# WL_CON.net
KiCad netlist of a schematic drawn in Altium Designer
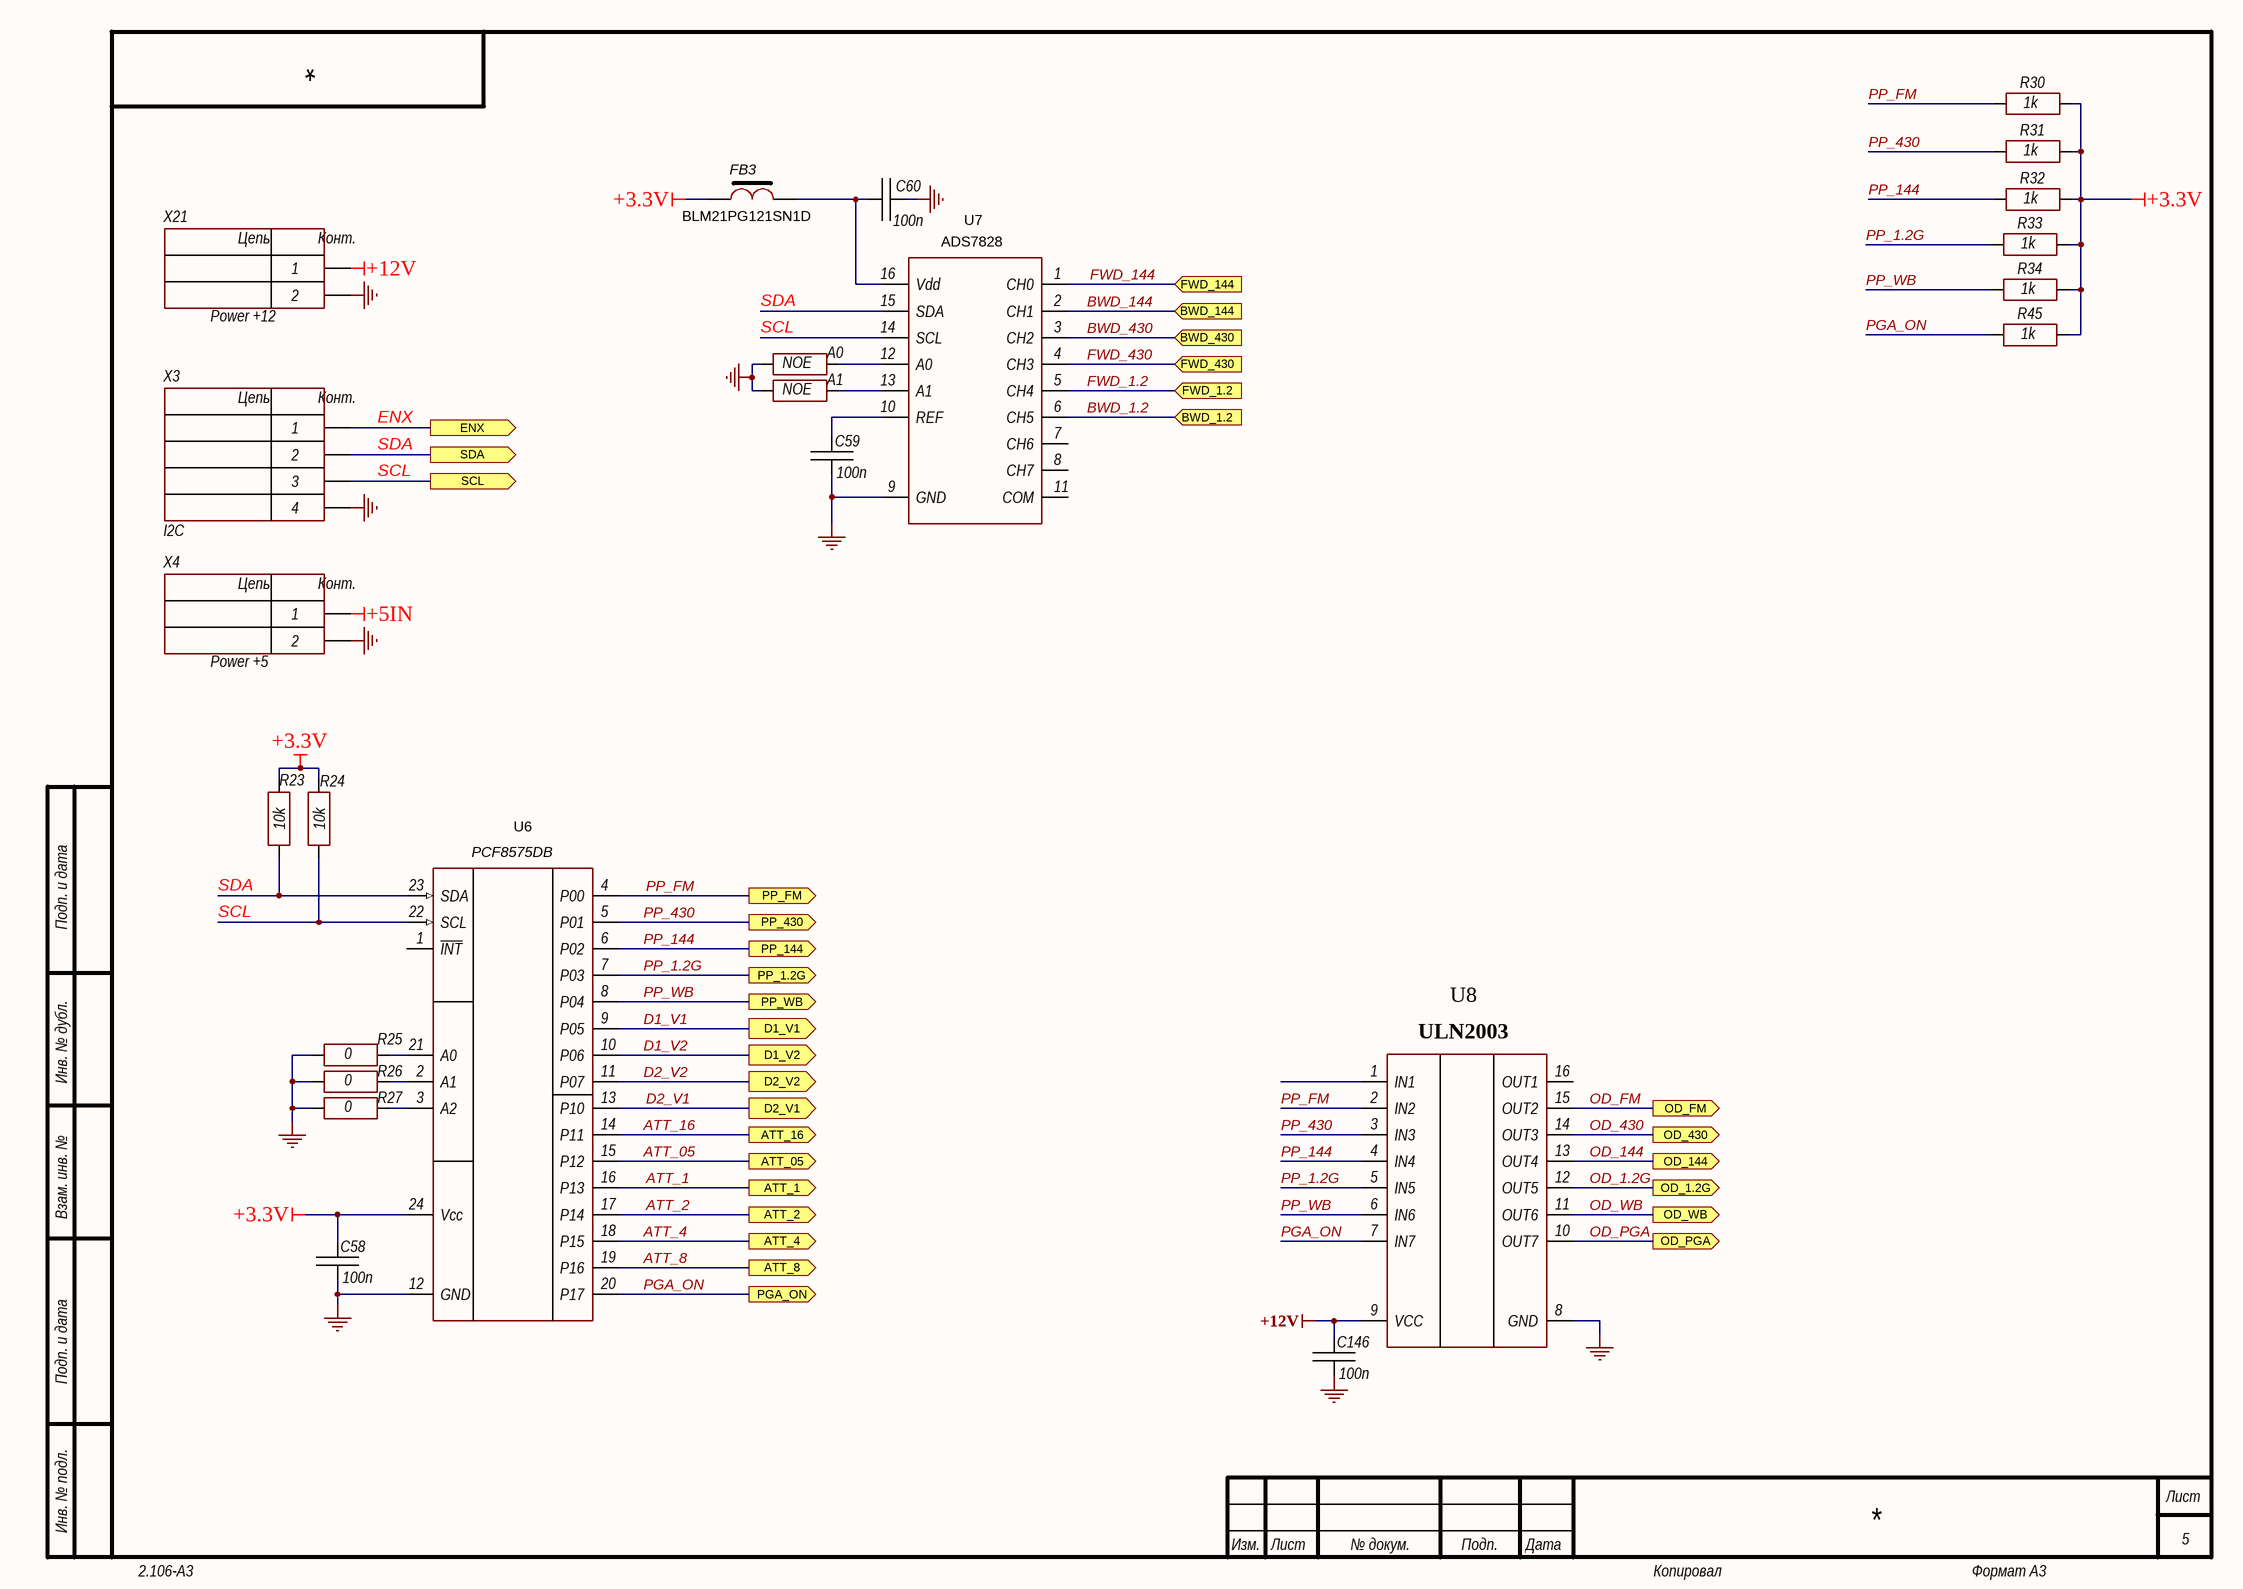
[diagram p0: WL_CON.SchDoc]

(export (version "E")
  (design (tool "Eeschema 10.0.6"))
  (components
    (comp (ref "A0")
      (value "NOE")
      (footprint "standard:CH0805R")
      (libsource (lib "Discrete") (part "Resistor"))
    )
    (comp (ref "A1")
      (value "NOE")
      (footprint "standard:CH0805R")
      (libsource (lib "Discrete") (part "Resistor"))
    )
    (comp (ref "C58")
      (value "100n")
      (footprint "standard:CH0805C")
      (libsource (lib "Discrete") (part "Capacitor"))
    )
    (comp (ref "C59")
      (value "100n")
      (footprint "standard:CH0805C")
      (libsource (lib "Discrete") (part "Capacitor"))
    )
    (comp (ref "C60")
      (value "100n")
      (footprint "standard:CH0805C")
      (libsource (lib "Discrete") (part "Capacitor"))
    )
    (comp (ref "C146")
      (value "100n")
      (footprint "standard:CH0805C")
      (libsource (lib "") (part "Capacitor_1"))
    )
    (comp (ref "FB3")
      (value "BLM21PG121SN1D")
      (footprint "CH0805L")
      (libsource (lib "Discrete") (part "FB-1"))
    )
    (comp (ref "R23") (value "10k") (footprint "standard:CH0805R") (libsource (lib "") (part "Resistor_1")))
    (comp (ref "R24") (value "10k") (footprint "standard:CH0805R") (libsource (lib "") (part "Resistor_1")))
    (comp (ref "R25")
      (value "0")
      (footprint "standard:CH0805R")
      (libsource (lib "Discrete") (part "Resistor"))
    )
    (comp (ref "R26")
      (value "0")
      (footprint "standard:CH0805R")
      (libsource (lib "Discrete") (part "Resistor"))
    )
    (comp (ref "R27")
      (value "0")
      (footprint "standard:CH0805R")
      (libsource (lib "Discrete") (part "Resistor"))
    )
    (comp (ref "R30")
      (value "1k")
      (footprint "standard:CH0603R")
      (libsource (lib "Discrete") (part "Resistor"))
    )
    (comp (ref "R31")
      (value "1k")
      (footprint "standard:CH0603R")
      (libsource (lib "Discrete") (part "Resistor"))
    )
    (comp (ref "R32")
      (value "1k")
      (footprint "standard:CH0603R")
      (libsource (lib "Discrete") (part "Resistor"))
    )
    (comp (ref "R33") (value "1k") (footprint "standard:CH0603R") (libsource (lib "") (part "Resistor_2")))
    (comp (ref "R34")
      (value "1k")
      (footprint "standard:CH0603R")
      (libsource (lib "Discrete") (part "Resistor"))
    )
    (comp (ref "R45")
      (value "1k")
      (footprint "standard:CH0603R")
      (libsource (lib "Discrete") (part "Resistor"))
    )
    (comp (ref "U6")
      (value "PCF8575DB")
      (footprint "24-TSSOP_HIR")
      (libsource (lib "Digital") (part "PCF8575"))
    )
    (comp (ref "U7") (value "ADS7828") (footprint "16-SSOP") (libsource (lib "Digital") (part "ADS7828")))
    (comp (ref "U8") (value "ULN2003") (footprint "16-SOIC") (libsource (lib "Digital") (part "ULN2003_NEW")))
    (comp (ref "X3")
      (value "I2C")
      (footprint "custom:CON: CWF-4")
      (libsource (lib "Connectors") (part "4-Connector"))
    )
    (comp (ref "X4")
      (value "Power +5")
      (footprint "custom:CON: CWF-2")
      (libsource (lib "Connectors") (part "2-Connector"))
    )
    (comp (ref "X21")
      (value "Power +12")
      (footprint "WL_RFFC:CON: CWF-2")
      (libsource (lib "Connectors") (part "2-Connector"))
    )
  )
  (nets
    (net (code "1") (name "+3.3V") (class "Default")
      (node (ref "C58") (pin "2") (pinfunction "2_2") (pintype "power_in"))
      (node (ref "FB3") (pin "1") (pinfunction "1_1") (pintype "passive"))
      (node (ref "R23") (pin "1") (pinfunction "1_1") (pintype "passive"))
      (node (ref "R24") (pin "1") (pinfunction "1_1") (pintype "passive"))
      (node (ref "R30") (pin "2") (pinfunction "2_2") (pintype "passive"))
      (node (ref "R31") (pin "2") (pinfunction "2_2") (pintype "passive"))
      (node (ref "R32") (pin "2") (pinfunction "2_2") (pintype "passive"))
      (node (ref "R33") (pin "2") (pinfunction "2_2") (pintype "passive"))
      (node (ref "R34") (pin "2") (pinfunction "2_2") (pintype "passive"))
      (node (ref "R45") (pin "2") (pinfunction "2_2") (pintype "passive"))
      (node (ref "U6") (pin "24") (pinfunction "Vcc_24") (pintype "passive"))
    )
    (net (code "2") (name "+5IN") (class "Default")
      (node (ref "X4") (pin "1") (pinfunction "1_1") (pintype "passive"))
    )
    (net (code "3") (name "+12V") (class "Default")
      (node (ref "C146") (pin "2") (pinfunction "2_2") (pintype "power_in"))
      (node (ref "U8") (pin "9") (pinfunction "VCC_9") (pintype "passive"))
      (node (ref "X21") (pin "1") (pinfunction "1_1") (pintype "passive"))
    )
    (net (code "4") (name "/ATT_1") (class "Default")
      (node (ref "U6") (pin "16") (pinfunction "P13_16") (pintype "passive"))
    )
    (net (code "5") (name "/ATT_2") (class "Default")
      (node (ref "U6") (pin "17") (pinfunction "P14_17") (pintype "passive"))
    )
    (net (code "6") (name "/ATT_4") (class "Default")
      (node (ref "U6") (pin "18") (pinfunction "P15_18") (pintype "passive"))
    )
    (net (code "7") (name "/ATT_05") (class "Default")
      (node (ref "U6") (pin "15") (pinfunction "P12_15") (pintype "passive"))
    )
    (net (code "8") (name "/ATT_8") (class "Default")
      (node (ref "U6") (pin "19") (pinfunction "P16_19") (pintype "passive"))
    )
    (net (code "9") (name "/ATT_16") (class "Default")
      (node (ref "U6") (pin "14") (pinfunction "P11_14") (pintype "passive"))
    )
    (net (code "10") (name "/BWD_1.2") (class "Default")
      (node (ref "U7") (pin "6") (pinfunction "CH5_6") (pintype "passive"))
    )
    (net (code "11") (name "/BWD_144") (class "Default")
      (node (ref "U7") (pin "2") (pinfunction "CH1_2") (pintype "passive"))
    )
    (net (code "12") (name "/BWD_430") (class "Default")
      (node (ref "U7") (pin "3") (pinfunction "CH2_3") (pintype "passive"))
    )
    (net (code "13") (name "/D1_V1") (class "Default")
      (node (ref "U6") (pin "9") (pinfunction "P05_9") (pintype "passive"))
    )
    (net (code "14") (name "/D1_V2") (class "Default")
      (node (ref "U6") (pin "10") (pinfunction "P06_10") (pintype "passive"))
    )
    (net (code "15") (name "/D2_V1") (class "Default")
      (node (ref "U6") (pin "13") (pinfunction "P10_13") (pintype "passive"))
    )
    (net (code "16") (name "/D2_V2") (class "Default")
      (node (ref "U6") (pin "11") (pinfunction "P07_11") (pintype "passive"))
    )
    (net (code "17") (name "/ENX") (class "Default")
      (node (ref "X3") (pin "1") (pinfunction "1_1") (pintype "passive"))
    )
    (net (code "18") (name "/FWD_1.2") (class "Default")
      (node (ref "U7") (pin "5") (pinfunction "CH4_5") (pintype "passive"))
    )
    (net (code "19") (name "/FWD_144") (class "Default")
      (node (ref "U7") (pin "1") (pinfunction "CH0_1") (pintype "passive"))
    )
    (net (code "20") (name "/FWD_430") (class "Default")
      (node (ref "U7") (pin "4") (pinfunction "CH3_4") (pintype "passive"))
    )
    (net (code "21") (name "/OD_1.2G") (class "Default")
      (node (ref "U8") (pin "12") (pinfunction "OUT5_12") (pintype "passive"))
    )
    (net (code "22") (name "/OD_144") (class "Default")
      (node (ref "U8") (pin "13") (pinfunction "OUT4_13") (pintype "passive"))
    )
    (net (code "23") (name "/OD_430") (class "Default")
      (node (ref "U8") (pin "14") (pinfunction "OUT3_14") (pintype "passive"))
    )
    (net (code "24") (name "/OD_FM") (class "Default")
      (node (ref "U8") (pin "15") (pinfunction "OUT2_15") (pintype "passive"))
    )
    (net (code "25") (name "/OD_PGA") (class "Default")
      (node (ref "U8") (pin "10") (pinfunction "OUT7_10") (pintype "passive"))
    )
    (net (code "26") (name "/OD_WB") (class "Default")
      (node (ref "U8") (pin "11") (pinfunction "OUT6_11") (pintype "passive"))
    )
    (net (code "27") (name "/PGA_ON") (class "Default")
      (node (ref "R45") (pin "1") (pinfunction "1_1") (pintype "passive"))
      (node (ref "U6") (pin "20") (pinfunction "P17_20") (pintype "passive"))
      (node (ref "U8") (pin "7") (pinfunction "IN7_7") (pintype "passive"))
    )
    (net (code "28") (name "/PP_1.2G") (class "Default")
      (node (ref "R33") (pin "1") (pinfunction "1_1") (pintype "passive"))
      (node (ref "U6") (pin "7") (pinfunction "P03_7") (pintype "passive"))
      (node (ref "U8") (pin "5") (pinfunction "IN5_5") (pintype "passive"))
    )
    (net (code "29") (name "/PP_144") (class "Default")
      (node (ref "R32") (pin "1") (pinfunction "1_1") (pintype "passive"))
      (node (ref "U6") (pin "6") (pinfunction "P02_6") (pintype "passive"))
      (node (ref "U8") (pin "4") (pinfunction "IN4_4") (pintype "passive"))
    )
    (net (code "30") (name "/PP_430") (class "Default")
      (node (ref "R31") (pin "1") (pinfunction "1_1") (pintype "passive"))
      (node (ref "U6") (pin "5") (pinfunction "P01_5") (pintype "passive"))
      (node (ref "U8") (pin "3") (pinfunction "IN3_3") (pintype "passive"))
    )
    (net (code "31") (name "/PP_FM") (class "Default")
      (node (ref "R30") (pin "1") (pinfunction "1_1") (pintype "passive"))
      (node (ref "U6") (pin "4") (pinfunction "P00_4") (pintype "passive"))
      (node (ref "U8") (pin "2") (pinfunction "IN2_2") (pintype "passive"))
    )
    (net (code "32") (name "/PP_WB") (class "Default")
      (node (ref "R34") (pin "1") (pinfunction "1_1") (pintype "passive"))
      (node (ref "U6") (pin "8") (pinfunction "P04_8") (pintype "passive"))
      (node (ref "U8") (pin "6") (pinfunction "IN6_6") (pintype "passive"))
    )
    (net (code "33") (name "/SCL") (class "Default")
      (node (ref "R24") (pin "2") (pinfunction "2_2") (pintype "passive"))
      (node (ref "U6") (pin "22") (pinfunction "SCL_22") (pintype "input"))
      (node (ref "U7") (pin "14") (pinfunction "SCL_14") (pintype "passive"))
      (node (ref "X3") (pin "3") (pinfunction "3_3") (pintype "power_in"))
    )
    (net (code "34") (name "/SDA") (class "Default")
      (node (ref "R23") (pin "2") (pinfunction "2_2") (pintype "passive"))
      (node (ref "U6") (pin "23") (pinfunction "SDA_23") (pintype "input"))
      (node (ref "U7") (pin "15") (pinfunction "SDA_15") (pintype "passive"))
      (node (ref "X3") (pin "2") (pinfunction "2_2") (pintype "passive"))
    )
    (net (code "35") (name "GND") (class "Default")
      (node (ref "A0") (pin "1") (pinfunction "1_1") (pintype "passive"))
      (node (ref "A1") (pin "1") (pinfunction "1_1") (pintype "passive"))
      (node (ref "C146") (pin "1") (pinfunction "1_1") (pintype "power_in"))
      (node (ref "C58") (pin "1") (pinfunction "1_1") (pintype "power_in"))
      (node (ref "C59") (pin "1") (pinfunction "1_1") (pintype "power_in"))
      (node (ref "C60") (pin "1") (pinfunction "1_1") (pintype "power_in"))
      (node (ref "R25") (pin "1") (pinfunction "1_1") (pintype "passive"))
      (node (ref "R26") (pin "1") (pinfunction "1_1") (pintype "passive"))
      (node (ref "R27") (pin "1") (pinfunction "1_1") (pintype "passive"))
      (node (ref "U6") (pin "12") (pinfunction "GND_12") (pintype "passive"))
      (node (ref "U7") (pin "9") (pinfunction "GND_9") (pintype "passive"))
      (node (ref "U8") (pin "8") (pinfunction "GND_8") (pintype "passive"))
      (node (ref "X21") (pin "2") (pinfunction "2_2") (pintype "passive"))
      (node (ref "X3") (pin "4") (pinfunction "4_4") (pintype "power_in"))
      (node (ref "X4") (pin "2") (pinfunction "2_2") (pintype "passive"))
    )
    (net (code "36") (name "Net-(U6-A0)") (class "Default")
      (node (ref "R25") (pin "2") (pinfunction "2_2") (pintype "passive"))
      (node (ref "U6") (pin "21") (pinfunction "A0_21") (pintype "passive"))
    )
    (net (code "37") (name "Net-(U6-A1)") (class "Default")
      (node (ref "R26") (pin "2") (pinfunction "2_2") (pintype "passive"))
      (node (ref "U6") (pin "2") (pinfunction "A1_2") (pintype "passive"))
    )
    (net (code "38") (name "Net-(U6-A2)") (class "Default")
      (node (ref "R27") (pin "2") (pinfunction "2_2") (pintype "passive"))
      (node (ref "U6") (pin "3") (pinfunction "A2_3") (pintype "passive"))
    )
    (net (code "39") (name "Net-(U7-A0)") (class "Default")
      (node (ref "A0") (pin "2") (pinfunction "2_2") (pintype "passive"))
      (node (ref "U7") (pin "12") (pinfunction "A0_12") (pintype "passive"))
    )
    (net (code "40") (name "Net-(U7-A1)") (class "Default")
      (node (ref "A1") (pin "2") (pinfunction "2_2") (pintype "passive"))
      (node (ref "U7") (pin "13") (pinfunction "A1_13") (pintype "passive"))
    )
    (net (code "41") (name "Net-(U7-REF)") (class "Default")
      (node (ref "C59") (pin "2") (pinfunction "2_2") (pintype "power_in"))
      (node (ref "U7") (pin "10") (pinfunction "REF_10") (pintype "passive"))
    )
    (net (code "42") (name "Net-(U7-Vdd)") (class "Default")
      (node (ref "C60") (pin "2") (pinfunction "2_2") (pintype "power_in"))
      (node (ref "FB3") (pin "2") (pinfunction "2_2") (pintype "passive"))
      (node (ref "U7") (pin "16") (pinfunction "Vdd_16") (pintype "passive"))
    )
    (net (code "43") (name "unconnected-(U6-~{INT}-Pad1)") (class "Default")
      (node (ref "U6") (pin "1") (pinfunction "~{INT}_1") (pintype "passive"))
    )
    (net (code "44") (name "unconnected-(U7-CH6-Pad7)") (class "Default")
      (node (ref "U7") (pin "7") (pinfunction "CH6_7") (pintype "passive"))
    )
    (net (code "45") (name "unconnected-(U7-CH7-Pad8)") (class "Default")
      (node (ref "U7") (pin "8") (pinfunction "CH7_8") (pintype "passive"))
    )
    (net (code "46") (name "unconnected-(U7-COM-Pad11)") (class "Default")
      (node (ref "U7") (pin "11") (pinfunction "COM_11") (pintype "passive"))
    )
    (net (code "47") (name "unconnected-(U8-IN1-Pad1)") (class "Default")
      (node (ref "U8") (pin "1") (pinfunction "IN1_1") (pintype "passive"))
    )
    (net (code "48") (name "unconnected-(U8-OUT1-Pad16)") (class "Default")
      (node (ref "U8") (pin "16") (pinfunction "OUT1_16") (pintype "passive"))
    )
  )
)
